# sardines-drying-circuit.net
KiCad netlist of a schematic drawn in EasyEDA Pro
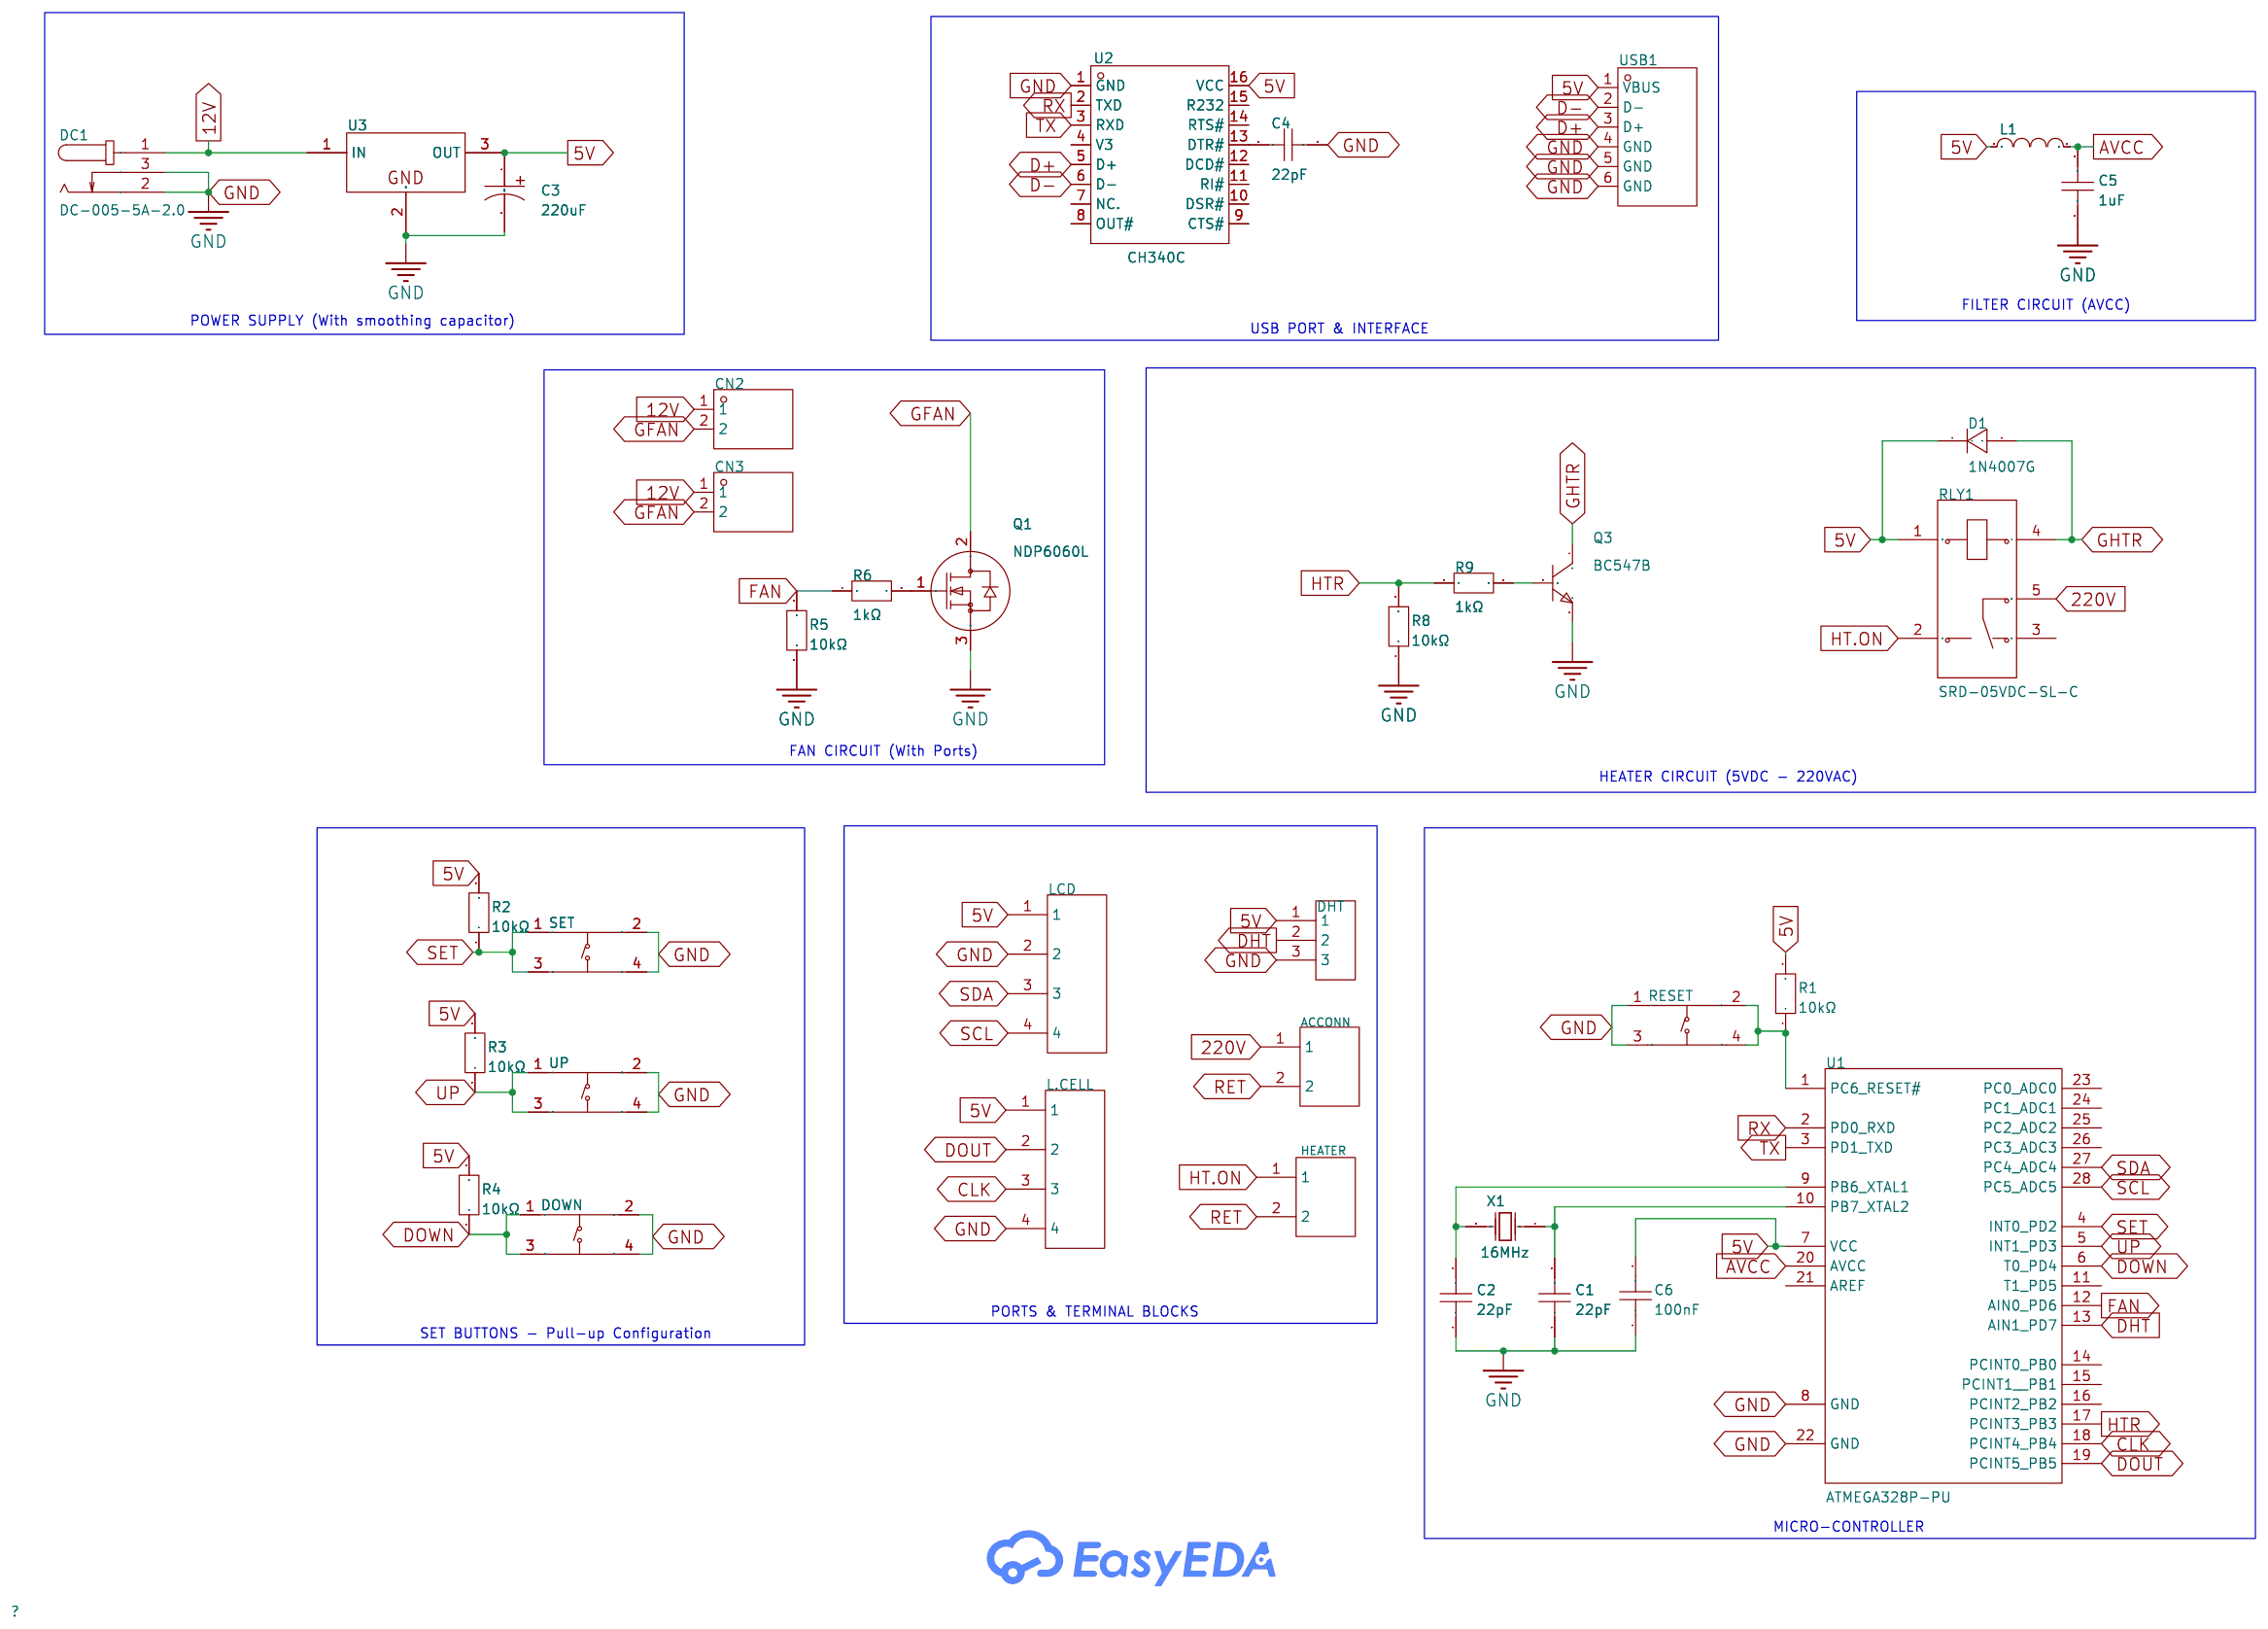
[diagram p0: schematic sheet]

(export (version "E")
  (design (tool "Eeschema 10.0.6"))
  (components
    (comp (ref "ACCONN")
      (value "WJ35C-B-8.25-2P")
      (footprint "easyedapro:CONN-TH_2P-P8.25_WJ35C-B-2P")
      (fields (field (name "Manufacturer") "KANGNEX(康奈克斯电气)"))
      (libsource (lib "easyedapro") (part "WJ35C-B-2P"))
    )
    (comp (ref "C1")
      (value "22pF")
      (footprint "easyedapro:CAP-TH_L5.8-W2.4-P2.54-D0.6")
      (fields
        (field (name "Manufacturer Part") "CC1H220KA1EDCH4B1100")
        (field (name "Manufacturer") "Dersonic(德尔创)")
      )
      (libsource (lib "easyedapro") (part "CC1H220KA1EDCH4B1100"))
    )
    (comp (ref "C2")
      (value "22pF")
      (footprint "easyedapro:CAP-TH_L5.8-W2.4-P2.54-D0.6")
      (fields
        (field (name "Manufacturer Part") "CC1H220KA1EDCH4B1100")
        (field (name "Manufacturer") "Dersonic(德尔创)")
      )
      (libsource (lib "easyedapro") (part "CC1H220KA1EDCH4B1100"))
    )
    (comp (ref "C3")
      (value "220uF")
      (footprint "easyedapro:CAP-TH_BD10.0-P5.00-D0.6-FD")
      (fields
        (field (name "Manufacturer Part") "50ZLJ220M10X12.5")
        (field (name "Manufacturer") "Rubycon(红宝石)")
      )
      (libsource (lib "easyedapro") (part "50ZLJ220M10X12.5"))
    )
    (comp (ref "C4")
      (value "22pF")
      (footprint "easyedapro:CAP-TH_L5.8-W2.4-P2.54-D0.6")
      (fields
        (field (name "Manufacturer Part") "CC1H220KA1EDCH4B1100")
        (field (name "Manufacturer") "Dersonic(德尔创)")
      )
      (libsource (lib "easyedapro") (part "CC1H220KA1EDCH4B1100"))
    )
    (comp (ref "C5")
      (value "1uF")
      (footprint "easyedapro:CAP-TH_L5.5-W3.5-P5.00-D1.2")
      (fields (field (name "Manufacturer Part") "FK26X7R1H105KRE06") (field (name "Manufacturer") "TDK"))
      (libsource (lib "easyedapro") (part "FK26X7R1H105KRE06"))
    )
    (comp (ref "C6")
      (value "100nF")
      (footprint "easyedapro:CAP-TH_L5.0-W2.5-P5.00-D1.0")
      (fields
        (field (name "Manufacturer Part") "CC1H104MC1FD3F6C10MF")
        (field (name "Manufacturer") "Dersonic(德尔创)")
      )
      (libsource (lib "easyedapro") (part "CC1H104MC1FD3F6C10MF"))
    )
    (comp (ref "CN2")
      (value "B2B-XH-A(LF)(SN)")
      (footprint "easyedapro:CONN-TH_B2B-XH-A-LF-SN")
      (fields (field (name "Manufacturer") "JST"))
      (libsource (lib "easyedapro") (part "B2B-XH-A (LF)(SN)"))
    )
    (comp (ref "CN3")
      (value "B2B-XH-A(LF)(SN)")
      (footprint "easyedapro:CONN-TH_B2B-XH-A-LF-SN")
      (fields (field (name "Manufacturer") "JST"))
      (libsource (lib "easyedapro") (part "B2B-XH-A (LF)(SN)"))
    )
    (comp (ref "D1")
      (value "1N4007G")
      (footprint "easyedapro:DO-41_BD2.4-L4.7-P8.70-D0.9-RD")
      (fields (field (name "Manufacturer") "onsemi(安森美)"))
      (libsource (lib "easyedapro") (part "1N4007G_C232439"))
    )
    (comp (ref "DC1")
      (value "DC-005-5A-2.0")
      (footprint "easyedapro:DC-IN-TH_DC-005-5A-2.0")
      (fields (field (name "Manufacturer") "XKB Connection(中国星坤)"))
      (libsource (lib "easyedapro") (part "DC-005-5A-2.0"))
    )
    (comp (ref "DHT")
      (value "B3B-XH-A(LF)(SN)")
      (footprint "easyedapro:CONN-TH_3P-P2.50_A2501WV2-3P")
      (fields (field (name "Manufacturer") "JST"))
      (libsource (lib "easyedapro") (part "B3B-XH-A(LF)(SN)"))
    )
    (comp (ref "DOWN")
      (value "TS665CJ")
      (footprint "easyedapro:SW-TH_4P-L6.0-W6.0-P4.50-LS6.5")
      (fields (field (name "Manufacturer") "SHOU HAN(首韩)"))
      (libsource (lib "easyedapro") (part "TS665CJ"))
    )
    (comp (ref "HEATER")
      (value "WJ35C-B-8.25-2P")
      (footprint "easyedapro:CONN-TH_2P-P8.25_WJ35C-B-2P")
      (fields (field (name "Manufacturer") "KANGNEX(康奈克斯电气)"))
      (libsource (lib "easyedapro") (part "WJ35C-B-2P"))
    )
    (comp (ref "L.CELL")
      (value "B4B-PH-K-S(LF)(SN)")
      (footprint "easyedapro:CONN-TH_B4B-PH-K-S")
      (fields (field (name "Manufacturer") "JST"))
      (libsource (lib "easyedapro") (part "B4B-PH-K-S(LF)(SN)"))
    )
    (comp (ref "L1")
      (value "BLM18PG121SN1D")
      (footprint "easyedapro:L0603")
      (fields (field (name "Manufacturer") "muRata(村田)"))
      (libsource (lib "easyedapro") (part "BLM18PG121SN1D_C14709"))
    )
    (comp (ref "LCD")
      (value "B4B-PH-K-S(LF)(SN)")
      (footprint "easyedapro:CONN-TH_B4B-PH-K-S")
      (fields (field (name "Manufacturer") "JST"))
      (libsource (lib "easyedapro") (part "B4B-PH-K-S(LF)(SN)"))
    )
    (comp (ref "Q1")
      (value "NDP6060L")
      (footprint "easyedapro:TO-220-3_L10.0-W4.5-P2.54-L")
      (fields (field (name "Manufacturer") "onsemi(安森美)"))
      (libsource (lib "easyedapro") (part "NDP6060L"))
    )
    (comp (ref "Q3")
      (value "BC547B")
      (footprint "easyedapro:TO-92-3_L4.9-W3.7-P1.27-L")
      (fields (field (name "Manufacturer") "LGE(鲁光)"))
      (libsource (lib "easyedapro") (part "BC547B"))
    )
    (comp (ref "R1")
      (value "10kΩ")
      (footprint "easyedapro:RES-TH_BD2.4-L6.3-P10.30-D0.6")
      (fields
        (field (name "Manufacturer Part") "RN1/4W10KFT/BA1")
        (field (name "Manufacturer") "Tyohm(幸亚电阻)")
      )
      (libsource (lib "easyedapro") (part "RN 1/4W 10K F T/B A1"))
    )
    (comp (ref "R2")
      (value "10kΩ")
      (footprint "easyedapro:RES-TH_BD2.4-L6.3-P10.30-D0.6")
      (fields
        (field (name "Manufacturer Part") "RN1/4W10KFT/BA1")
        (field (name "Manufacturer") "Tyohm(幸亚电阻)")
      )
      (libsource (lib "easyedapro") (part "RN 1/4W 10K F T/B A1"))
    )
    (comp (ref "R3")
      (value "10kΩ")
      (footprint "easyedapro:RES-TH_BD2.4-L6.3-P10.30-D0.6")
      (fields
        (field (name "Manufacturer Part") "RN1/4W10KFT/BA1")
        (field (name "Manufacturer") "Tyohm(幸亚电阻)")
      )
      (libsource (lib "easyedapro") (part "RN 1/4W 10K F T/B A1"))
    )
    (comp (ref "R4")
      (value "10kΩ")
      (footprint "easyedapro:RES-TH_BD2.4-L6.3-P10.30-D0.6")
      (fields
        (field (name "Manufacturer Part") "RN1/4W10KFT/BA1")
        (field (name "Manufacturer") "Tyohm(幸亚电阻)")
      )
      (libsource (lib "easyedapro") (part "RN 1/4W 10K F T/B A1"))
    )
    (comp (ref "R5")
      (value "10kΩ")
      (footprint "easyedapro:RES-TH_BD2.4-L6.3-P10.30-D0.6")
      (fields
        (field (name "Manufacturer Part") "RN1/4W10KFT/BA1")
        (field (name "Manufacturer") "Tyohm(幸亚电阻)")
      )
      (libsource (lib "easyedapro") (part "RN 1/4W 10K F T/B A1"))
    )
    (comp (ref "R6")
      (value "1kΩ")
      (footprint "easyedapro:RES-TH_BD2.7-L6.2-P10.20-D0.4")
      (fields (field (name "Manufacturer Part") "MF1/4W-1K±1%-ST52") (field (name "Manufacturer") "VO(翔胜)"))
      (libsource (lib "easyedapro") (part "MF1/4W-1K±1%-ST52"))
    )
    (comp (ref "R8")
      (value "10kΩ")
      (footprint "easyedapro:RES-TH_BD2.4-L6.3-P10.30-D0.6")
      (fields
        (field (name "Manufacturer Part") "RN1/4W10KFT/BA1")
        (field (name "Manufacturer") "Tyohm(幸亚电阻)")
      )
      (libsource (lib "easyedapro") (part "RN 1/4W 10K F T/B A1"))
    )
    (comp (ref "R9")
      (value "1kΩ")
      (footprint "easyedapro:RES-TH_BD2.7-L6.2-P10.20-D0.4")
      (fields (field (name "Manufacturer Part") "MF1/4W-1K±1%-ST52") (field (name "Manufacturer") "VO(翔胜)"))
      (libsource (lib "easyedapro") (part "MF1/4W-1K±1%-ST52"))
    )
    (comp (ref "RESET")
      (value "TS665CJ")
      (footprint "easyedapro:SW-TH_4P-L6.0-W6.0-P4.50-LS6.5")
      (fields (field (name "Manufacturer") "SHOU HAN(首韩)"))
      (libsource (lib "easyedapro") (part "TS665CJ"))
    )
    (comp (ref "RLY1")
      (value "SRD-05VDC-SL-C")
      (footprint "easyedapro:RELAY-TH_SRD-XXVDC-XL-C")
      (fields (field (name "Manufacturer") "松乐"))
      (libsource (lib "easyedapro") (part "SRD-05VDC-SL-C"))
    )
    (comp (ref "SET")
      (value "TS665CJ")
      (footprint "easyedapro:SW-TH_4P-L6.0-W6.0-P4.50-LS6.5")
      (fields (field (name "Manufacturer") "SHOU HAN(首韩)"))
      (libsource (lib "easyedapro") (part "TS665CJ"))
    )
    (comp (ref "U1")
      (value "ATMEGA328P-PU")
      (footprint "easyedapro:DIP-28_L34.6-W7.3-P2.54-LS10.2-BL")
      (fields (field (name "Manufacturer") "MICROCHIP(美国微芯)"))
      (libsource (lib "easyedapro") (part "ATMEGA328P-PU"))
    )
    (comp (ref "U2")
      (value "CH340C")
      (footprint "easyedapro:SOP-16_L10.0-W3.9-P1.27-LS6.0-BL")
      (fields (field (name "Manufacturer") "WCH(南京沁恒)"))
      (libsource (lib "easyedapro") (part "CH340C"))
    )
    (comp (ref "U3")
      (value "L7805CV-DG")
      (footprint "easyedapro:TO-220-3_L10.0-W4.5-P2.54-L")
      (fields (field (name "Manufacturer") "ST(意法半导体)"))
      (libsource (lib "easyedapro") (part "L7805CV-DG"))
    )
    (comp (ref "UP")
      (value "TS665CJ")
      (footprint "easyedapro:SW-TH_4P-L6.0-W6.0-P4.50-LS6.5")
      (fields (field (name "Manufacturer") "SHOU HAN(首韩)"))
      (libsource (lib "easyedapro") (part "TS665CJ"))
    )
    (comp (ref "USB1")
      (value "USB-B10-BRW")
      (footprint "easyedapro:USB-B-TH_USB-B10-BRW")
      (fields (field (name "Manufacturer") "XUNPU(讯普)"))
      (libsource (lib "easyedapro") (part "USB-B10-BRW"))
    )
    (comp (ref "X1")
      (value "16MHz")
      (footprint "easyedapro:OSC-TH_L10.0-W4.5-P5.00")
      (fields (field (name "Manufacturer Part") "X49SD16MSD2SC") (field (name "Manufacturer") "YXC(扬兴晶振)"))
      (libsource (lib "easyedapro") (part "X49SD16MSD2SC"))
    )
  )
  (nets
    (net (code "1") (name "5V") (class "Default")
      (node (ref "C3") (pin "1") (pinfunction "1_1") (pintype "unspecified"))
      (node (ref "C6") (pin "2") (pinfunction "2_2") (pintype "unspecified"))
      (node (ref "D1") (pin "1") (pinfunction "1_1") (pintype "unspecified"))
      (node (ref "DHT") (pin "1") (pinfunction "1_1") (pintype "unspecified"))
      (node (ref "L.CELL") (pin "1") (pinfunction "1_1") (pintype "input"))
      (node (ref "L1") (pin "1") (pinfunction "1_1") (pintype "unspecified"))
      (node (ref "LCD") (pin "1") (pinfunction "1_1") (pintype "input"))
      (node (ref "R1") (pin "2") (pinfunction "2_2") (pintype "unspecified"))
      (node (ref "R2") (pin "2") (pinfunction "2_2") (pintype "unspecified"))
      (node (ref "R3") (pin "2") (pinfunction "2_2") (pintype "unspecified"))
      (node (ref "R4") (pin "2") (pinfunction "2_2") (pintype "unspecified"))
      (node (ref "RLY1") (pin "1") (pinfunction "1_1") (pintype "input"))
      (node (ref "U1") (pin "7") (pinfunction "VCC_7") (pintype "unspecified"))
      (node (ref "U2") (pin "16") (pinfunction "VCC_16") (pintype "unspecified"))
      (node (ref "U3") (pin "3") (pinfunction "OUT_3") (pintype "unspecified"))
      (node (ref "USB1") (pin "1") (pinfunction "VBUS_1") (pintype "unspecified"))
    )
    (net (code "2") (name "12V") (class "Default")
      (node (ref "CN2") (pin "1") (pinfunction "1_1") (pintype "unspecified"))
      (node (ref "CN3") (pin "1") (pinfunction "1_1") (pintype "unspecified"))
      (node (ref "DC1") (pin "1") (pinfunction "1_1") (pintype "unspecified"))
      (node (ref "U3") (pin "1") (pinfunction "IN_1") (pintype "unspecified"))
    )
    (net (code "3") (name "220V") (class "Default")
      (node (ref "ACCONN") (pin "1") (pinfunction "1_1") (pintype "input"))
      (node (ref "RLY1") (pin "5") (pinfunction "5_5") (pintype "input"))
    )
    (net (code "4") (name "AVCC") (class "Default")
      (node (ref "C5") (pin "2") (pinfunction "2_2") (pintype "unspecified"))
      (node (ref "L1") (pin "2") (pinfunction "2_2") (pintype "unspecified"))
      (node (ref "U1") (pin "20") (pinfunction "AVCC_20") (pintype "unspecified"))
    )
    (net (code "5") (name "CLK") (class "Default")
      (node (ref "L.CELL") (pin "3") (pinfunction "3_3") (pintype "input"))
      (node (ref "U1") (pin "18") (pinfunction "PCINT4_PB4_18") (pintype "bidirectional"))
    )
    (net (code "6") (name "D+") (class "Default")
      (node (ref "U2") (pin "5") (pinfunction "D+_5") (pintype "unspecified"))
      (node (ref "USB1") (pin "3") (pinfunction "D+_3") (pintype "unspecified"))
    )
    (net (code "7") (name "D-") (class "Default")
      (node (ref "U2") (pin "6") (pinfunction "D-_6") (pintype "unspecified"))
      (node (ref "USB1") (pin "2") (pinfunction "D-_2") (pintype "unspecified"))
    )
    (net (code "8") (name "DHT") (class "Default")
      (node (ref "DHT") (pin "2") (pinfunction "2_2") (pintype "unspecified"))
      (node (ref "U1") (pin "13") (pinfunction "AIN1_PD7_13") (pintype "bidirectional"))
    )
    (net (code "9") (name "DOUT") (class "Default")
      (node (ref "L.CELL") (pin "2") (pinfunction "2_2") (pintype "input"))
      (node (ref "U1") (pin "19") (pinfunction "PCINT5_PB5_19") (pintype "bidirectional"))
    )
    (net (code "10") (name "DOWN") (class "Default")
      (node (ref "DOWN") (pin "1") (pinfunction "A_1") (pintype "unspecified"))
      (node (ref "DOWN") (pin "3") (pinfunction "C_3") (pintype "unspecified"))
      (node (ref "R4") (pin "1") (pinfunction "1_1") (pintype "unspecified"))
      (node (ref "U1") (pin "6") (pinfunction "T0_PD4_6") (pintype "bidirectional"))
    )
    (net (code "11") (name "FAN") (class "Default")
      (node (ref "R5") (pin "2") (pinfunction "2_2") (pintype "unspecified"))
      (node (ref "R6") (pin "1") (pinfunction "1_1") (pintype "unspecified"))
      (node (ref "U1") (pin "12") (pinfunction "AIN0_PD6_12") (pintype "bidirectional"))
    )
    (net (code "12") (name "GFAN") (class "Default")
      (node (ref "CN2") (pin "2") (pinfunction "2_2") (pintype "unspecified"))
      (node (ref "CN3") (pin "2") (pinfunction "2_2") (pintype "unspecified"))
      (node (ref "Q1") (pin "2") (pinfunction "D_2") (pintype "unspecified"))
    )
    (net (code "13") (name "GHTR") (class "Default")
      (node (ref "D1") (pin "2") (pinfunction "2_2") (pintype "unspecified"))
      (node (ref "Q3") (pin "1") (pinfunction "C_1") (pintype "input"))
      (node (ref "RLY1") (pin "4") (pinfunction "4_4") (pintype "input"))
    )
    (net (code "14") (name "GND") (class "Default")
      (node (ref "C1") (pin "1") (pinfunction "1_1") (pintype "unspecified"))
      (node (ref "C2") (pin "1") (pinfunction "1_1") (pintype "unspecified"))
      (node (ref "C3") (pin "2") (pinfunction "2_2") (pintype "unspecified"))
      (node (ref "C4") (pin "1") (pinfunction "1_1") (pintype "unspecified"))
      (node (ref "C5") (pin "1") (pinfunction "1_1") (pintype "unspecified"))
      (node (ref "C6") (pin "1") (pinfunction "1_1") (pintype "unspecified"))
      (node (ref "DC1") (pin "2") (pinfunction "2_2") (pintype "unspecified"))
      (node (ref "DC1") (pin "3") (pinfunction "3_3") (pintype "unspecified"))
      (node (ref "DHT") (pin "3") (pinfunction "3_3") (pintype "unspecified"))
      (node (ref "DOWN") (pin "2") (pinfunction "B_2") (pintype "unspecified"))
      (node (ref "DOWN") (pin "4") (pinfunction "D_4") (pintype "unspecified"))
      (node (ref "L.CELL") (pin "4") (pinfunction "4_4") (pintype "input"))
      (node (ref "LCD") (pin "2") (pinfunction "2_2") (pintype "input"))
      (node (ref "Q1") (pin "3") (pinfunction "S_3") (pintype "unspecified"))
      (node (ref "Q3") (pin "3") (pinfunction "E_3") (pintype "input"))
      (node (ref "R5") (pin "1") (pinfunction "1_1") (pintype "unspecified"))
      (node (ref "R8") (pin "1") (pinfunction "1_1") (pintype "unspecified"))
      (node (ref "RESET") (pin "1") (pinfunction "A_1") (pintype "unspecified"))
      (node (ref "RESET") (pin "3") (pinfunction "C_3") (pintype "unspecified"))
      (node (ref "SET") (pin "2") (pinfunction "B_2") (pintype "unspecified"))
      (node (ref "SET") (pin "4") (pinfunction "D_4") (pintype "unspecified"))
      (node (ref "U1") (pin "22") (pinfunction "GND_22") (pintype "unspecified"))
      (node (ref "U1") (pin "8") (pinfunction "GND_8") (pintype "unspecified"))
      (node (ref "U2") (pin "1") (pinfunction "GND_1") (pintype "unspecified"))
      (node (ref "U3") (pin "2") (pinfunction "GND_2") (pintype "unspecified"))
      (node (ref "UP") (pin "2") (pinfunction "B_2") (pintype "unspecified"))
      (node (ref "UP") (pin "4") (pinfunction "D_4") (pintype "unspecified"))
      (node (ref "USB1") (pin "4") (pinfunction "GND_4") (pintype "unspecified"))
      (node (ref "USB1") (pin "5") (pinfunction "GND_5") (pintype "unspecified"))
      (node (ref "USB1") (pin "6") (pinfunction "GND_6") (pintype "unspecified"))
    )
    (net (code "15") (name "HT.ON") (class "Default")
      (node (ref "HEATER") (pin "1") (pinfunction "1_1") (pintype "input"))
      (node (ref "RLY1") (pin "2") (pinfunction "2_2") (pintype "input"))
    )
    (net (code "16") (name "HTR") (class "Default")
      (node (ref "R8") (pin "2") (pinfunction "2_2") (pintype "unspecified"))
      (node (ref "R9") (pin "1") (pinfunction "1_1") (pintype "unspecified"))
      (node (ref "U1") (pin "17") (pinfunction "PCINT3_PB3_17") (pintype "bidirectional"))
    )
    (net (code "17") (name "Net-(Q1-G)") (class "Default")
      (node (ref "Q1") (pin "1") (pinfunction "G_1") (pintype "unspecified"))
      (node (ref "R6") (pin "2") (pinfunction "2_2") (pintype "unspecified"))
    )
    (net (code "18") (name "Net-(Q3-B)") (class "Default")
      (node (ref "Q3") (pin "2") (pinfunction "B_2") (pintype "input"))
      (node (ref "R9") (pin "2") (pinfunction "2_2") (pintype "unspecified"))
    )
    (net (code "19") (name "Net-(RESET-B)") (class "Default")
      (node (ref "R1") (pin "1") (pinfunction "1_1") (pintype "unspecified"))
      (node (ref "RESET") (pin "2") (pinfunction "B_2") (pintype "unspecified"))
      (node (ref "RESET") (pin "4") (pinfunction "D_4") (pintype "unspecified"))
      (node (ref "U1") (pin "1") (pinfunction "PC6_RESET#_1") (pintype "bidirectional"))
    )
    (net (code "20") (name "Net-(U1-PB6_XTAL1)") (class "Default")
      (node (ref "C2") (pin "2") (pinfunction "2_2") (pintype "unspecified"))
      (node (ref "U1") (pin "9") (pinfunction "PB6_XTAL1_9") (pintype "bidirectional"))
      (node (ref "X1") (pin "2") (pinfunction "OSC2_2") (pintype "input"))
    )
    (net (code "21") (name "Net-(U1-PB7_XTAL2)") (class "Default")
      (node (ref "C1") (pin "2") (pinfunction "2_2") (pintype "unspecified"))
      (node (ref "U1") (pin "10") (pinfunction "PB7_XTAL2_10") (pintype "bidirectional"))
      (node (ref "X1") (pin "1") (pinfunction "OSC1_1") (pintype "input"))
    )
    (net (code "22") (name "Net-(U2-DTR#)") (class "Default")
      (node (ref "C4") (pin "2") (pinfunction "2_2") (pintype "unspecified"))
      (node (ref "U2") (pin "13") (pinfunction "DTR#_13") (pintype "unspecified"))
    )
    (net (code "23") (name "RET") (class "Default")
      (node (ref "ACCONN") (pin "2") (pinfunction "2_2") (pintype "input"))
      (node (ref "HEATER") (pin "2") (pinfunction "2_2") (pintype "input"))
    )
    (net (code "24") (name "RX") (class "Default")
      (node (ref "U1") (pin "2") (pinfunction "PD0_RXD_2") (pintype "bidirectional"))
      (node (ref "U2") (pin "2") (pinfunction "TXD_2") (pintype "unspecified"))
    )
    (net (code "25") (name "SCL") (class "Default")
      (node (ref "LCD") (pin "4") (pinfunction "4_4") (pintype "input"))
      (node (ref "U1") (pin "28") (pinfunction "PC5_ADC5_28") (pintype "bidirectional"))
    )
    (net (code "26") (name "SDA") (class "Default")
      (node (ref "LCD") (pin "3") (pinfunction "3_3") (pintype "input"))
      (node (ref "U1") (pin "27") (pinfunction "PC4_ADC4_27") (pintype "bidirectional"))
    )
    (net (code "27") (name "SET") (class "Default")
      (node (ref "R2") (pin "1") (pinfunction "1_1") (pintype "unspecified"))
      (node (ref "SET") (pin "1") (pinfunction "A_1") (pintype "unspecified"))
      (node (ref "SET") (pin "3") (pinfunction "C_3") (pintype "unspecified"))
      (node (ref "U1") (pin "4") (pinfunction "INT0_PD2_4") (pintype "bidirectional"))
    )
    (net (code "28") (name "TX") (class "Default")
      (node (ref "U1") (pin "3") (pinfunction "PD1_TXD_3") (pintype "bidirectional"))
      (node (ref "U2") (pin "3") (pinfunction "RXD_3") (pintype "unspecified"))
    )
    (net (code "29") (name "UP") (class "Default")
      (node (ref "R3") (pin "1") (pinfunction "1_1") (pintype "unspecified"))
      (node (ref "U1") (pin "5") (pinfunction "INT1_PD3_5") (pintype "bidirectional"))
      (node (ref "UP") (pin "1") (pinfunction "A_1") (pintype "unspecified"))
      (node (ref "UP") (pin "3") (pinfunction "C_3") (pintype "unspecified"))
    )
    (net (code "30") (name "unconnected-(RLY1-Pad3)") (class "Default")
      (node (ref "RLY1") (pin "3") (pinfunction "3_3") (pintype "input"))
    )
    (net (code "31") (name "unconnected-(U1-AREF-Pad21)") (class "Default")
      (node (ref "U1") (pin "21") (pinfunction "AREF_21") (pintype "unspecified"))
    )
    (net (code "32") (name "unconnected-(U1-PC0_ADC0-Pad23)") (class "Default")
      (node (ref "U1") (pin "23") (pinfunction "PC0_ADC0_23") (pintype "bidirectional"))
    )
    (net (code "33") (name "unconnected-(U1-PC1_ADC1-Pad24)") (class "Default")
      (node (ref "U1") (pin "24") (pinfunction "PC1_ADC1_24") (pintype "bidirectional"))
    )
    (net (code "34") (name "unconnected-(U1-PC2_ADC2-Pad25)") (class "Default")
      (node (ref "U1") (pin "25") (pinfunction "PC2_ADC2_25") (pintype "bidirectional"))
    )
    (net (code "35") (name "unconnected-(U1-PC3_ADC3-Pad26)") (class "Default")
      (node (ref "U1") (pin "26") (pinfunction "PC3_ADC3_26") (pintype "bidirectional"))
    )
    (net (code "36") (name "unconnected-(U1-PCINT0_PB0-Pad14)") (class "Default")
      (node (ref "U1") (pin "14") (pinfunction "PCINT0_PB0_14") (pintype "bidirectional"))
    )
    (net (code "37") (name "unconnected-(U1-PCINT1__PB1-Pad15)") (class "Default")
      (node (ref "U1") (pin "15") (pinfunction "PCINT1__PB1_15") (pintype "bidirectional"))
    )
    (net (code "38") (name "unconnected-(U1-PCINT2_PB2-Pad16)") (class "Default")
      (node (ref "U1") (pin "16") (pinfunction "PCINT2_PB2_16") (pintype "bidirectional"))
    )
    (net (code "39") (name "unconnected-(U1-T1_PD5-Pad11)") (class "Default")
      (node (ref "U1") (pin "11") (pinfunction "T1_PD5_11") (pintype "bidirectional"))
    )
    (net (code "40") (name "unconnected-(U2-CTS#-Pad9)") (class "Default")
      (node (ref "U2") (pin "9") (pinfunction "CTS#_9") (pintype "unspecified"))
    )
    (net (code "41") (name "unconnected-(U2-DCD#-Pad12)") (class "Default")
      (node (ref "U2") (pin "12") (pinfunction "DCD#_12") (pintype "unspecified"))
    )
    (net (code "42") (name "unconnected-(U2-DSR#-Pad10)") (class "Default")
      (node (ref "U2") (pin "10") (pinfunction "DSR#_10") (pintype "unspecified"))
    )
    (net (code "43") (name "unconnected-(U2-NC.-Pad7)") (class "Default")
      (node (ref "U2") (pin "7") (pinfunction "NC._7") (pintype "unspecified"))
    )
    (net (code "44") (name "unconnected-(U2-OUT#-Pad8)") (class "Default")
      (node (ref "U2") (pin "8") (pinfunction "OUT#_8") (pintype "unspecified"))
    )
    (net (code "45") (name "unconnected-(U2-R232-Pad15)") (class "Default")
      (node (ref "U2") (pin "15") (pinfunction "R232_15") (pintype "unspecified"))
    )
    (net (code "46") (name "unconnected-(U2-RI#-Pad11)") (class "Default")
      (node (ref "U2") (pin "11") (pinfunction "RI#_11") (pintype "unspecified"))
    )
    (net (code "47") (name "unconnected-(U2-RTS#-Pad14)") (class "Default")
      (node (ref "U2") (pin "14") (pinfunction "RTS#_14") (pintype "unspecified"))
    )
    (net (code "48") (name "unconnected-(U2-V3-Pad4)") (class "Default")
      (node (ref "U2") (pin "4") (pinfunction "V3_4") (pintype "unspecified"))
    )
  )
)
